# pcb.net
KiCad netlist of a schematic drawn in EAGLE
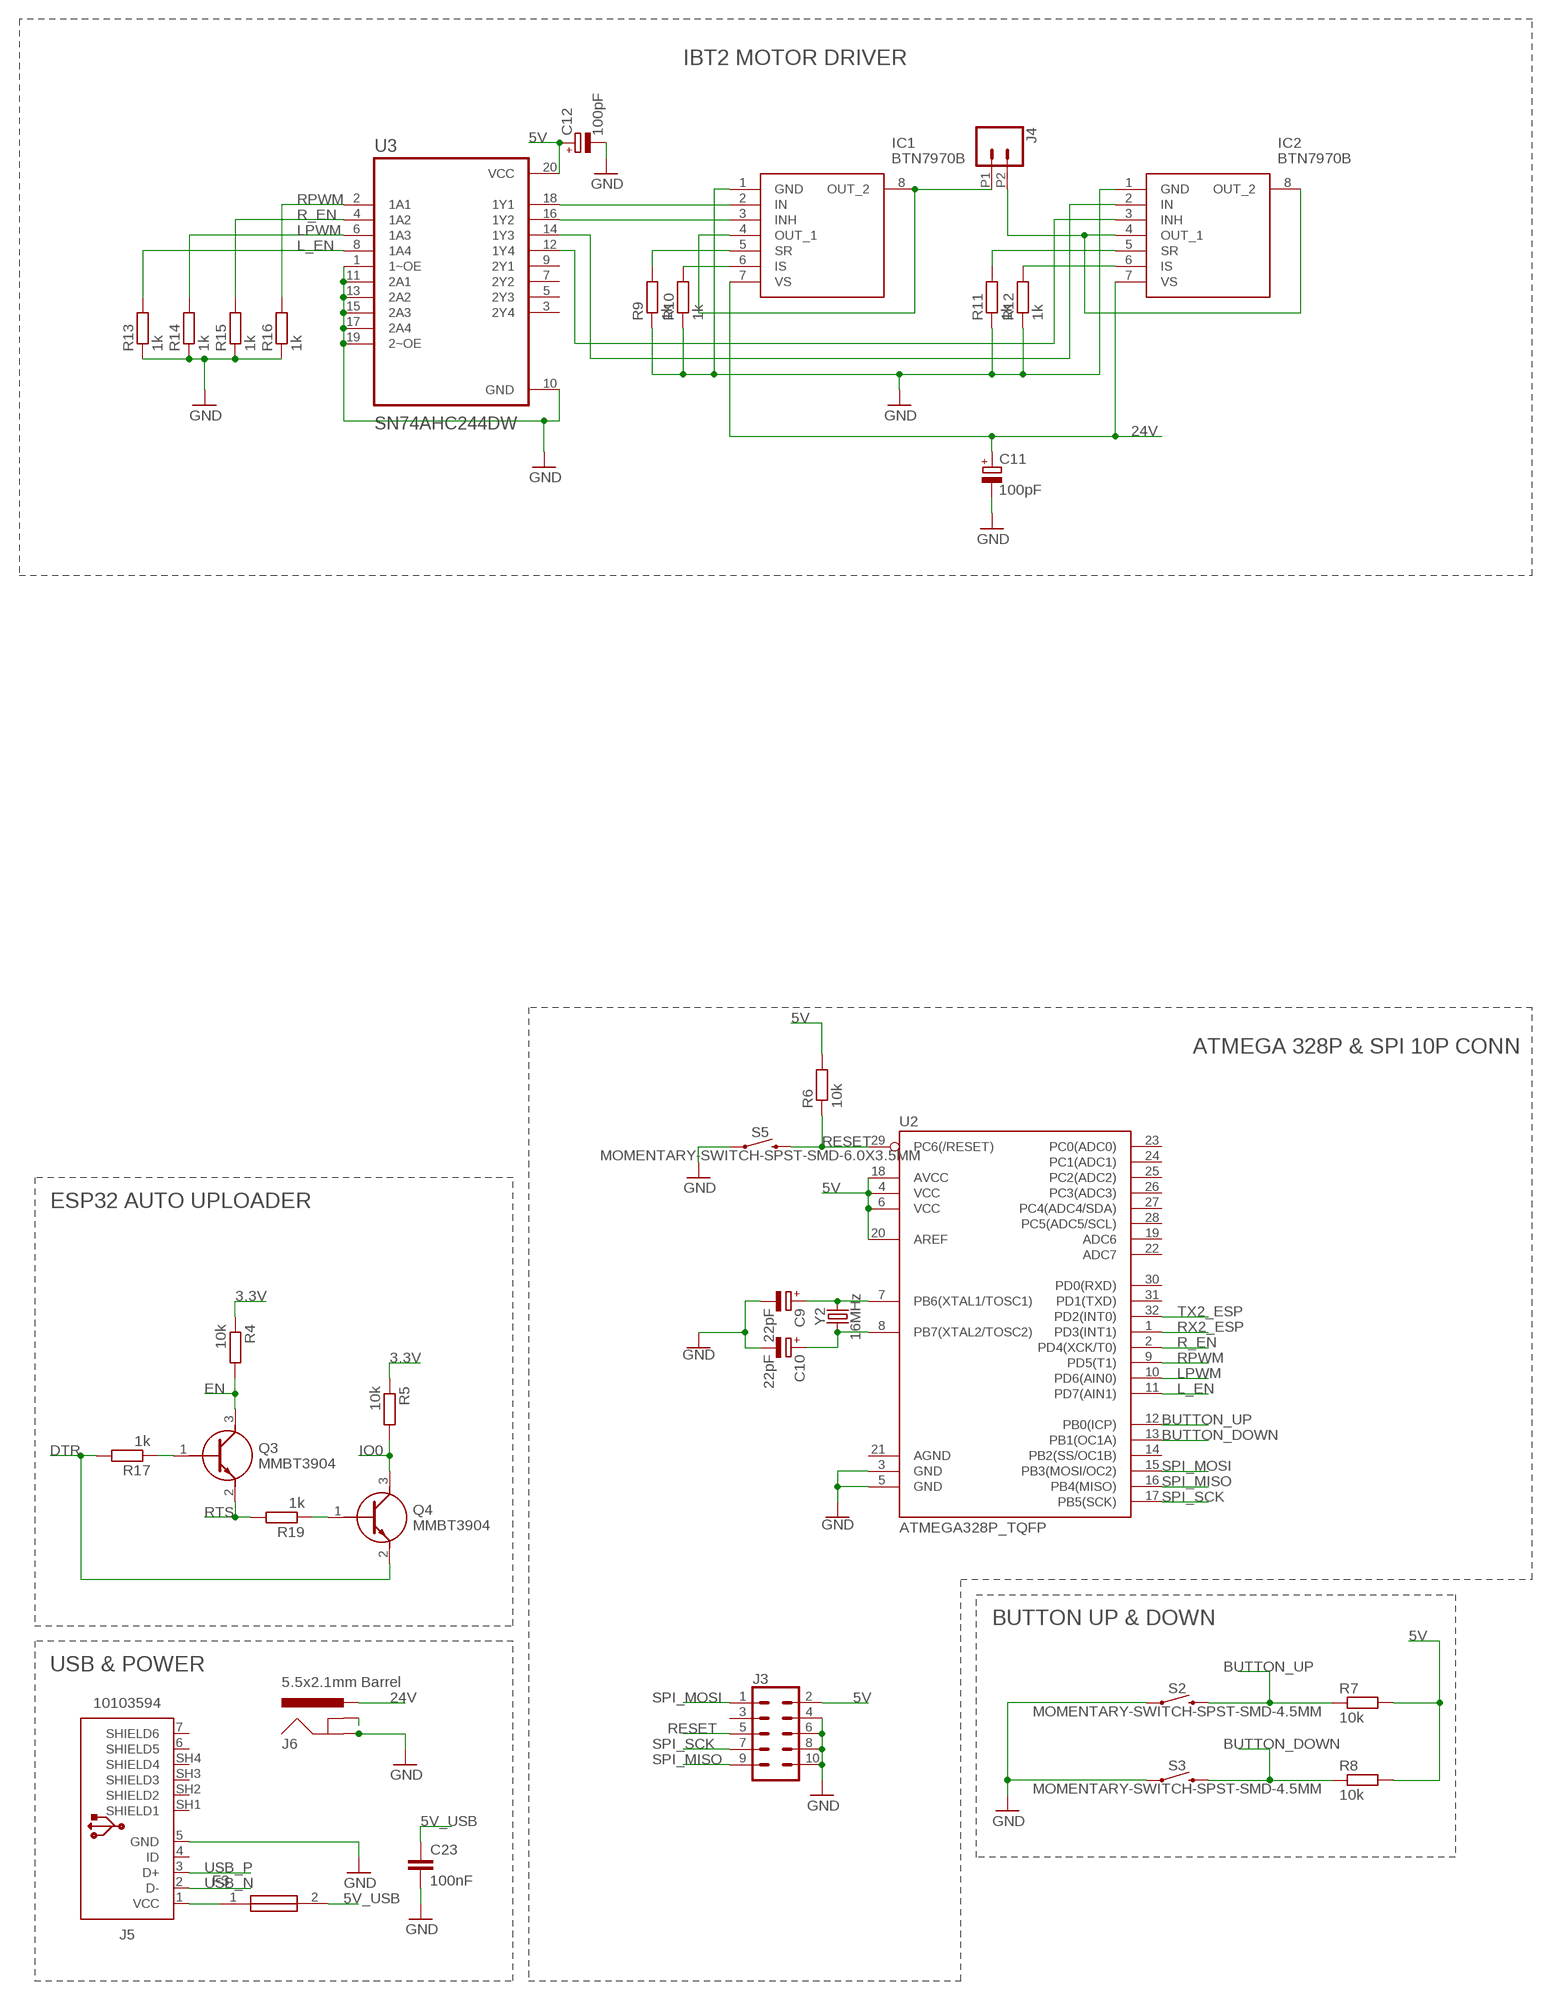
[diagram p0: schematic, sheet 1, part 1 of 2]
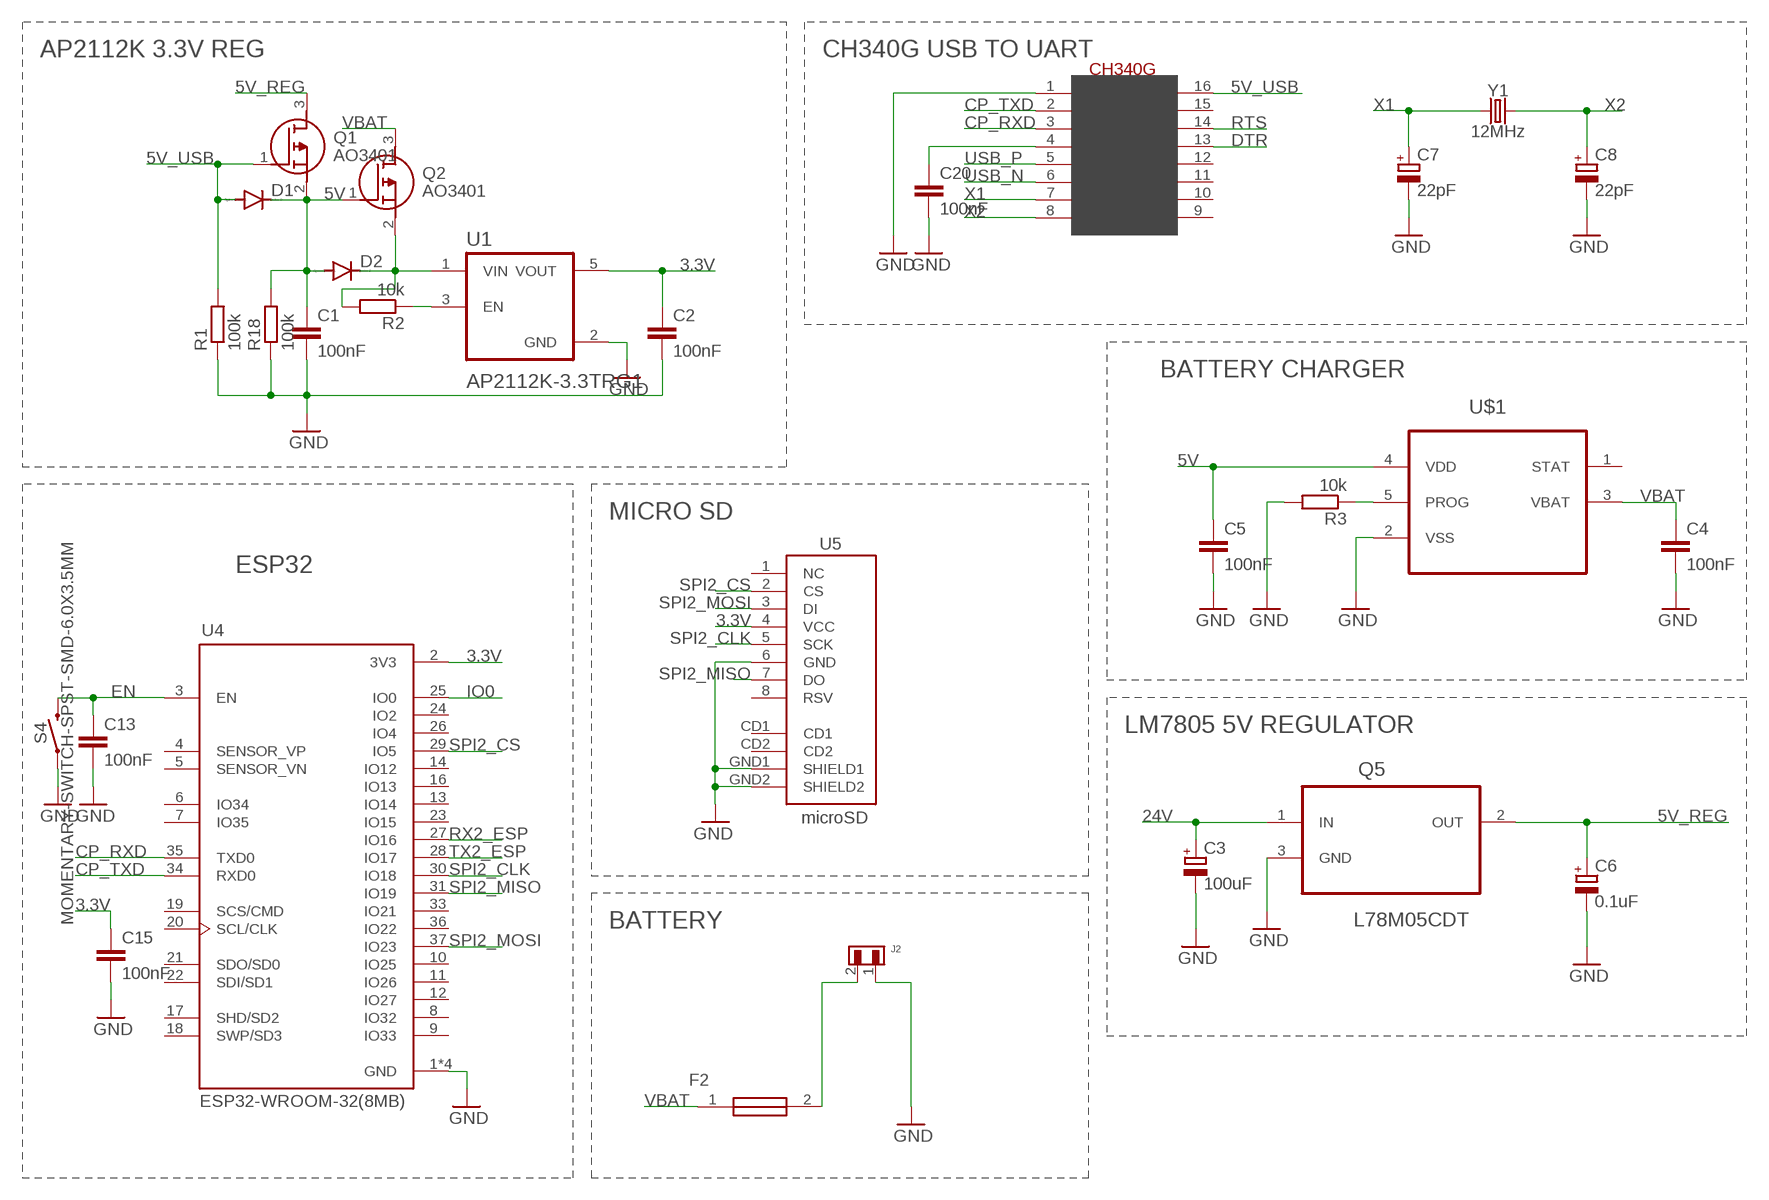
[diagram p1: schematic, sheet 1, part 2 of 2]

(export (version "E")
  (design (tool "Eeschema 10.0.6"))
  (components
    (comp (ref "C1")
      (value "100nF")
      (footprint "eagle-import:C0603")
      (libsource (lib "eagle-import") (part "C-EUC0603"))
    )
    (comp (ref "C2")
      (value "100nF")
      (footprint "eagle-import:C0603")
      (libsource (lib "eagle-import") (part "C-EUC0603"))
    )
    (comp (ref "C3")
      (value "100uF")
      (footprint "eagle-import:SMC_C")
      (libsource (lib "eagle-import") (part "CPOL-EUSMCC"))
    )
    (comp (ref "C4")
      (value "100nF")
      (footprint "eagle-import:C0603")
      (libsource (lib "eagle-import") (part "C-EUC0603"))
    )
    (comp (ref "C5")
      (value "100nF")
      (footprint "eagle-import:C0603")
      (libsource (lib "eagle-import") (part "C-EUC0603"))
    )
    (comp (ref "C6")
      (value "0.1uF")
      (footprint "eagle-import:SMC_C")
      (libsource (lib "eagle-import") (part "CPOL-EUSMCC"))
    )
    (comp (ref "C7")
      (value "22pF")
      (footprint "eagle-import:SMC_C")
      (libsource (lib "eagle-import") (part "CPOL-EUSMCC"))
    )
    (comp (ref "C8")
      (value "22pF")
      (footprint "eagle-import:SMC_C")
      (libsource (lib "eagle-import") (part "CPOL-EUSMCC"))
    )
    (comp (ref "C9")
      (value "22pF")
      (footprint "eagle-import:SMC_C")
      (libsource (lib "eagle-import") (part "CPOL-EUSMCC"))
    )
    (comp (ref "C10")
      (value "22pF")
      (footprint "eagle-import:SMC_C")
      (libsource (lib "eagle-import") (part "CPOL-EUSMCC"))
    )
    (comp (ref "C11")
      (value "100pF")
      (footprint "eagle-import:SMC_C")
      (libsource (lib "eagle-import") (part "CPOL-EUSMCC"))
    )
    (comp (ref "C12")
      (value "100pF")
      (footprint "eagle-import:SMC_C")
      (libsource (lib "eagle-import") (part "CPOL-EUSMCC"))
    )
    (comp (ref "C13")
      (value "100nF")
      (footprint "eagle-import:C0603")
      (libsource (lib "eagle-import") (part "C-EUC0603"))
    )
    (comp (ref "C15")
      (value "100nF")
      (footprint "eagle-import:C0603")
      (libsource (lib "eagle-import") (part "C-EUC0603"))
    )
    (comp (ref "C20")
      (value "100nF")
      (footprint "eagle-import:C0603")
      (libsource (lib "eagle-import") (part "C-EUC0603"))
    )
    (comp (ref "C23")
      (value "100nF")
      (footprint "eagle-import:C0603")
      (libsource (lib "eagle-import") (part "C-EUC0603"))
    )
    (comp (ref "D1")
      (value "DIODE-DO214AC")
      (footprint "eagle-import:DO214AC")
      (libsource (lib "eagle-import") (part "DIODE-DO214AC"))
    )
    (comp (ref "D2")
      (value "DIODE-DO214AC")
      (footprint "eagle-import:DO214AC")
      (libsource (lib "eagle-import") (part "DIODE-DO214AC"))
    )
    (comp (ref "F2")
      (value "MF-NSML260_12-2")
      (footprint "eagle-import:FUSC3216X100N")
      (fields
        (field (name "ARROW_PART_NUMBER") "MF-NSML260/12-2")
        (field (name "MOUSER_PART_NUMBER") "652-MF-NSML260/12-2")
      )
      (libsource (lib "eagle-import") (part "MF-NSML260_12-2"))
    )
    (comp (ref "F3")
      (value "MF-NSML260_12-2")
      (footprint "eagle-import:FUSC3216X100N")
      (fields
        (field (name "ARROW_PART_NUMBER") "MF-NSML260/12-2")
        (field (name "MOUSER_PART_NUMBER") "652-MF-NSML260/12-2")
      )
      (libsource (lib "eagle-import") (part "MF-NSML260_12-2"))
    )
    (comp (ref "IC1")
      (value "BTN7970B")
      (footprint "eagle-import:PG-TO263-7-1")
      (fields (field (name "MOUSER_PART_NUMBER") "726-BTN7970B"))
      (libsource (lib "eagle-import") (part "BTN7970B"))
    )
    (comp (ref "IC2")
      (value "BTN7970B")
      (footprint "eagle-import:PG-TO263-7-1")
      (fields (field (name "MOUSER_PART_NUMBER") "726-BTN7970B"))
      (libsource (lib "eagle-import") (part "BTN7970B"))
    )
    (comp (ref "J2")
      (value "620102131822")
      (footprint "eagle-import:620102131822")
      (libsource (lib "eagle-import") (part "620102131822"))
    )
    (comp (ref "J3")
      (value "CONN_05X2SHD-NS")
      (footprint "eagle-import:2X5-SHROUDED-NS")
      (libsource (lib "eagle-import") (part "CONN_05X2SHD-NS"))
    )
    (comp (ref "J4")
      (value "CONN_022.54MM_SCREWTERM")
      (footprint "eagle-import:1X02_2.54_SCREWTERM")
      (libsource (lib "eagle-import") (part "CONN_022.54MM_SCREWTERM"))
    )
    (comp (ref "J5")
      (value "10103594")
      (footprint "eagle-import:10103594")
      (fields (field (name "MANUFACTURER") "Amphenol ICC (FCI)") (field (name "MPN") "10103594-0001LF"))
      (libsource (lib "eagle-import") (part "10103594"))
    )
    (comp (ref "J6")
      (value "5.5x2.1mm Barrel")
      (footprint "eagle-import:POWER_JACK_SMD")
      (libsource (lib "eagle-import") (part "POWER_JACKSMD"))
    )
    (comp (ref "Q1")
      (value "AO3401")
      (footprint "eagle-import:SOT95P280X125-3N")
      (fields (field (name "ARROW_PART_NUMBER") "AO3401A"))
      (libsource (lib "eagle-import") (part "AO3401A"))
    )
    (comp (ref "Q2")
      (value "AO3401")
      (footprint "eagle-import:SOT95P280X125-3N")
      (fields (field (name "ARROW_PART_NUMBER") "AO3401A"))
      (libsource (lib "eagle-import") (part "AO3401A"))
    )
    (comp (ref "Q3")
      (value "MMBT3904")
      (footprint "eagle-import:SOT95P240X120-3N")
      (fields (field (name "MOUSER_PART_NUMBER") "512-MMBT3904"))
      (libsource (lib "eagle-import") (part "MMBT3904"))
    )
    (comp (ref "Q4")
      (value "MMBT3904")
      (footprint "eagle-import:SOT95P240X120-3N")
      (fields (field (name "MOUSER_PART_NUMBER") "512-MMBT3904"))
      (libsource (lib "eagle-import") (part "MMBT3904"))
    )
    (comp (ref "Q5")
      (value "L78M05CDT")
      (footprint "eagle-import:TO225P972X240-3N")
      (fields (field (name "MF") "STMicroelectronics"))
      (libsource (lib "eagle-import") (part "L78M05CDT"))
    )
    (comp (ref "R1")
      (value "100k")
      (footprint "eagle-import:R0603")
      (libsource (lib "eagle-import") (part "R-EU_R0603"))
    )
    (comp (ref "R2")
      (value "10k")
      (footprint "eagle-import:R0603")
      (libsource (lib "eagle-import") (part "R-EU_R0603"))
    )
    (comp (ref "R3")
      (value "10k")
      (footprint "eagle-import:R0603")
      (libsource (lib "eagle-import") (part "R-EU_R0603"))
    )
    (comp (ref "R4")
      (value "10k")
      (footprint "eagle-import:R0603")
      (libsource (lib "eagle-import") (part "R-EU_R0603"))
    )
    (comp (ref "R5")
      (value "10k")
      (footprint "eagle-import:R0603")
      (libsource (lib "eagle-import") (part "R-EU_R0603"))
    )
    (comp (ref "R6")
      (value "10k")
      (footprint "eagle-import:R0603")
      (libsource (lib "eagle-import") (part "R-EU_R0603"))
    )
    (comp (ref "R7")
      (value "10k")
      (footprint "eagle-import:R0603")
      (libsource (lib "eagle-import") (part "R-EU_R0603"))
    )
    (comp (ref "R8")
      (value "10k")
      (footprint "eagle-import:R0603")
      (libsource (lib "eagle-import") (part "R-EU_R0603"))
    )
    (comp (ref "R9")
      (value "1k")
      (footprint "eagle-import:R0603")
      (libsource (lib "eagle-import") (part "R-EU_R0603"))
    )
    (comp (ref "R10")
      (value "1k")
      (footprint "eagle-import:R0603")
      (libsource (lib "eagle-import") (part "R-EU_R0603"))
    )
    (comp (ref "R11")
      (value "1k")
      (footprint "eagle-import:R0603")
      (libsource (lib "eagle-import") (part "R-EU_R0603"))
    )
    (comp (ref "R12")
      (value "1k")
      (footprint "eagle-import:R0603")
      (libsource (lib "eagle-import") (part "R-EU_R0603"))
    )
    (comp (ref "R13")
      (value "1k")
      (footprint "eagle-import:R0603")
      (libsource (lib "eagle-import") (part "R-EU_R0603"))
    )
    (comp (ref "R14")
      (value "1k")
      (footprint "eagle-import:R0603")
      (libsource (lib "eagle-import") (part "R-EU_R0603"))
    )
    (comp (ref "R15")
      (value "1k")
      (footprint "eagle-import:R0603")
      (libsource (lib "eagle-import") (part "R-EU_R0603"))
    )
    (comp (ref "R16")
      (value "1k")
      (footprint "eagle-import:R0603")
      (libsource (lib "eagle-import") (part "R-EU_R0603"))
    )
    (comp (ref "R17")
      (value "1k")
      (footprint "eagle-import:R0603")
      (libsource (lib "eagle-import") (part "R-EU_R0603"))
    )
    (comp (ref "R18")
      (value "100k")
      (footprint "eagle-import:R0603")
      (libsource (lib "eagle-import") (part "R-EU_R0603"))
    )
    (comp (ref "R19")
      (value "1k")
      (footprint "eagle-import:R0603")
      (libsource (lib "eagle-import") (part "R-EU_R0603"))
    )
    (comp (ref "S2")
      (value "MOMENTARY-SWITCH-SPST-SMD-4.5MM")
      (footprint "eagle-import:TACTILE_SWITCH_SMD_4.5MM")
      (libsource (lib "eagle-import") (part "MOMENTARY-SWITCH-SPST-SMD-4.5MM"))
    )
    (comp (ref "S3")
      (value "MOMENTARY-SWITCH-SPST-SMD-4.5MM")
      (footprint "eagle-import:TACTILE_SWITCH_SMD_4.5MM")
      (libsource (lib "eagle-import") (part "MOMENTARY-SWITCH-SPST-SMD-4.5MM"))
    )
    (comp (ref "S4")
      (value "MOMENTARY-SWITCH-SPST-SMD-6.0X3.5MM")
      (footprint "eagle-import:TACTILE_SWITCH_SMD_6.0X3.5MM")
      (libsource (lib "eagle-import") (part "MOMENTARY-SWITCH-SPST-SMD-6.0X3.5MM"))
    )
    (comp (ref "S5")
      (value "MOMENTARY-SWITCH-SPST-SMD-6.0X3.5MM")
      (footprint "eagle-import:TACTILE_SWITCH_SMD_6.0X3.5MM")
      (libsource (lib "eagle-import") (part "MOMENTARY-SWITCH-SPST-SMD-6.0X3.5MM"))
    )
    (comp (ref "U$1")
      (value "MCP73831T-5ACI/OT")
      (footprint "eagle-import:SOT95P280X145-5N")
      (fields (field (name "MF") "Microchip"))
      (libsource (lib "eagle-import") (part "MCP73831T-5ACI/OT"))
    )
    (comp (ref "U$2")
      (value "CH340G")
      (footprint "eagle-import:SOIC16")
      (libsource (lib "eagle-import") (part "CH340G"))
    )
    (comp (ref "U1")
      (value "AP2112K-3.3TRG1")
      (footprint "eagle-import:SOT95P285X140-5N")
      (fields (field (name "MF") "Diodes Inc."))
      (libsource (lib "eagle-import") (part "AP2112K-3.3TRG1"))
    )
    (comp (ref "U2")
      (value "ATMEGA328P_TQFP")
      (footprint "eagle-import:TQFP32-08")
      (libsource (lib "eagle-import") (part "ATMEGA328P_TQFP"))
    )
    (comp (ref "U3")
      (value "SN74AHC244DW")
      (footprint "eagle-import:SOIC127P1030X265-20N")
      (fields (field (name "MF") "Texas Instruments"))
      (libsource (lib "eagle-import") (part "SN74AHC244DW"))
    )
    (comp (ref "U4")
      (value "ESP32-WROOM-32(8MB)")
      (footprint "eagle-import:MODULE_ESP32-WROOM-32(8MB)")
      (fields (field (name "MF") "Espressif Systems") (field (name "MP") "ESP32-WROOM-32 (8MB)"))
      (libsource (lib "eagle-import") (part "ESP32-WROOM-32(8MB)"))
    )
    (comp (ref "U5")
      (value "microSD")
      (footprint "eagle-import:MICRO-SD-SOCKET-PP")
      (libsource (lib "eagle-import") (part "USD-SOCKETSMD"))
    )
    (comp (ref "Y1")
      (value "12MHz")
      (footprint "eagle-import:CRYSTAL-SMD-5X3.2-4PAD")
      (libsource (lib "eagle-import") (part "CRYSTAL-12MHZ{dblquote}"))
    )
    (comp (ref "Y2")
      (value "16MHz")
      (footprint "eagle-import:CRYSTAL-SMD-5X3.2-4PAD")
      (libsource (lib "eagle-import") (part "CRYSTAL-16MHZSMD-5X3.2"))
    )
  )
  (nets
    (net (code "1") (name "/3.3V") (class "Default")
      (node (ref "C15") (pin "1") (pinfunction "1_1") (pintype "passive"))
      (node (ref "C2") (pin "1") (pinfunction "1_1") (pintype "passive"))
      (node (ref "R4") (pin "1") (pinfunction "1_1") (pintype "passive"))
      (node (ref "R5") (pin "1") (pinfunction "1_1") (pintype "passive"))
      (node (ref "U1") (pin "5") (pinfunction "VOUT_5") (pintype "power_in"))
      (node (ref "U4") (pin "2") (pinfunction "3V3_2") (pintype "power_in"))
      (node (ref "U5") (pin "4") (pinfunction "VCC_4") (pintype "bidirectional"))
    )
    (net (code "2") (name "/5V") (class "Default")
      (node (ref "C1") (pin "1") (pinfunction "1_1") (pintype "passive"))
      (node (ref "C12") (pin "+") (pinfunction "+_+") (pintype "passive"))
      (node (ref "C5") (pin "1") (pinfunction "1_1") (pintype "passive"))
      (node (ref "D1") (pin "C") (pinfunction "C_C") (pintype "passive"))
      (node (ref "D2") (pin "A") (pinfunction "A_A") (pintype "passive"))
      (node (ref "J3") (pin "2") (pinfunction "2_2") (pintype "passive"))
      (node (ref "Q1") (pin "2") (pinfunction "S_2") (pintype "bidirectional"))
      (node (ref "Q2") (pin "1") (pinfunction "G_1") (pintype "bidirectional"))
      (node (ref "R18") (pin "2") (pinfunction "2_2") (pintype "passive"))
      (node (ref "R6") (pin "2") (pinfunction "2_2") (pintype "passive"))
      (node (ref "R7") (pin "2") (pinfunction "2_2") (pintype "passive"))
      (node (ref "R8") (pin "2") (pinfunction "2_2") (pintype "passive"))
      (node (ref "U$1") (pin "4") (pinfunction "VDD_4") (pintype "power_in"))
      (node (ref "U2") (pin "18") (pinfunction "AVCC_18") (pintype "bidirectional"))
      (node (ref "U2") (pin "20") (pinfunction "AREF_20") (pintype "bidirectional"))
      (node (ref "U2") (pin "4") (pinfunction "VCC_4") (pintype "bidirectional"))
      (node (ref "U2") (pin "6") (pinfunction "VCC_6") (pintype "bidirectional"))
      (node (ref "U3") (pin "20") (pinfunction "VCC_20") (pintype "power_in"))
    )
    (net (code "3") (name "/5V_REG") (class "Default")
      (node (ref "C6") (pin "+") (pinfunction "+_+") (pintype "passive"))
      (node (ref "Q1") (pin "3") (pinfunction "D_3") (pintype "bidirectional"))
      (node (ref "Q5") (pin "2") (pinfunction "OUT_2") (pintype "output"))
    )
    (net (code "4") (name "/5V_USB") (class "Default")
      (node (ref "C23") (pin "1") (pinfunction "1_1") (pintype "passive"))
      (node (ref "D1") (pin "A") (pinfunction "A_A") (pintype "passive"))
      (node (ref "F3") (pin "2") (pinfunction "2_2") (pintype "bidirectional"))
      (node (ref "Q1") (pin "1") (pinfunction "G_1") (pintype "bidirectional"))
      (node (ref "R1") (pin "2") (pinfunction "2_2") (pintype "passive"))
      (node (ref "U$2") (pin "16") (pinfunction "VCC_16") (pintype "bidirectional"))
    )
    (net (code "5") (name "/24V") (class "Default")
      (node (ref "C11") (pin "+") (pinfunction "+_+") (pintype "passive"))
      (node (ref "C3") (pin "+") (pinfunction "+_+") (pintype "passive"))
      (node (ref "IC1") (pin "7") (pinfunction "VS_7") (pintype "bidirectional"))
      (node (ref "IC2") (pin "7") (pinfunction "VS_7") (pintype "bidirectional"))
      (node (ref "J6") (pin "VIN0") (pinfunction "PWR_VIN0") (pintype "bidirectional"))
      (node (ref "Q5") (pin "1") (pinfunction "IN_1") (pintype "input"))
    )
    (net (code "6") (name "/BUTTON_DOWN") (class "Default")
      (node (ref "R8") (pin "1") (pinfunction "1_1") (pintype "passive"))
      (node (ref "S3") (pin "1") (pinfunction "2_1") (pintype "passive"))
      (node (ref "S3") (pin "4") (pinfunction "2_4") (pintype "passive"))
      (node (ref "U2") (pin "13") (pinfunction "PB1(OC1A)_13") (pintype "bidirectional"))
    )
    (net (code "7") (name "/BUTTON_UP") (class "Default")
      (node (ref "R7") (pin "1") (pinfunction "1_1") (pintype "passive"))
      (node (ref "S2") (pin "1") (pinfunction "2_1") (pintype "passive"))
      (node (ref "S2") (pin "4") (pinfunction "2_4") (pintype "passive"))
      (node (ref "U2") (pin "12") (pinfunction "PB0(ICP)_12") (pintype "bidirectional"))
    )
    (net (code "8") (name "/CP_RXD") (class "Default")
      (node (ref "U$2") (pin "3") (pinfunction "RX_3") (pintype "bidirectional"))
      (node (ref "U4") (pin "35") (pinfunction "TXD0_35") (pintype "bidirectional"))
    )
    (net (code "9") (name "/CP_TXD") (class "Default")
      (node (ref "U$2") (pin "2") (pinfunction "TX_2") (pintype "bidirectional"))
      (node (ref "U4") (pin "34") (pinfunction "RXD0_34") (pintype "bidirectional"))
    )
    (net (code "10") (name "/DTR") (class "Default")
      (node (ref "Q4") (pin "2") (pinfunction "E_2") (pintype "bidirectional"))
      (node (ref "R17") (pin "2") (pinfunction "2_2") (pintype "passive"))
      (node (ref "U$2") (pin "13") (pinfunction "DTR_13") (pintype "bidirectional"))
    )
    (net (code "11") (name "/EN") (class "Default")
      (node (ref "C13") (pin "1") (pinfunction "1_1") (pintype "passive"))
      (node (ref "Q3") (pin "3") (pinfunction "C_3") (pintype "bidirectional"))
      (node (ref "R4") (pin "2") (pinfunction "2_2") (pintype "passive"))
      (node (ref "S4") (pin "2") (pinfunction "2_2") (pintype "passive"))
      (node (ref "U4") (pin "3") (pinfunction "EN_3") (pintype "input"))
    )
    (net (code "12") (name "/IO0") (class "Default")
      (node (ref "Q4") (pin "3") (pinfunction "C_3") (pintype "bidirectional"))
      (node (ref "R5") (pin "2") (pinfunction "2_2") (pintype "passive"))
      (node (ref "U4") (pin "25") (pinfunction "IO0_25") (pintype "bidirectional"))
    )
    (net (code "13") (name "/LPWM") (class "Default")
      (node (ref "R14") (pin "2") (pinfunction "2_2") (pintype "passive"))
      (node (ref "U2") (pin "10") (pinfunction "PD6(AIN0)_10") (pintype "bidirectional"))
      (node (ref "U3") (pin "6") (pinfunction "1A3_6") (pintype "input"))
    )
    (net (code "14") (name "/L_EN") (class "Default")
      (node (ref "R13") (pin "2") (pinfunction "2_2") (pintype "passive"))
      (node (ref "U2") (pin "11") (pinfunction "PD7(AIN1)_11") (pintype "bidirectional"))
      (node (ref "U3") (pin "8") (pinfunction "1A4_8") (pintype "input"))
    )
    (net (code "15") (name "/RESET") (class "Default")
      (node (ref "J3") (pin "5") (pinfunction "5_5") (pintype "passive"))
      (node (ref "R6") (pin "1") (pinfunction "1_1") (pintype "passive"))
      (node (ref "S5") (pin "2") (pinfunction "2_2") (pintype "passive"))
      (node (ref "U2") (pin "29") (pinfunction "PC6(/RESET)_29") (pintype "bidirectional"))
    )
    (net (code "16") (name "/RPWM") (class "Default")
      (node (ref "R16") (pin "2") (pinfunction "2_2") (pintype "passive"))
      (node (ref "U2") (pin "9") (pinfunction "PD5(T1)_9") (pintype "bidirectional"))
      (node (ref "U3") (pin "2") (pinfunction "1A1_2") (pintype "input"))
    )
    (net (code "17") (name "/RTS") (class "Default")
      (node (ref "Q3") (pin "2") (pinfunction "E_2") (pintype "bidirectional"))
      (node (ref "R19") (pin "2") (pinfunction "2_2") (pintype "passive"))
      (node (ref "U$2") (pin "14") (pinfunction "RTS_14") (pintype "bidirectional"))
    )
    (net (code "18") (name "/RX2_ESP") (class "Default")
      (node (ref "U2") (pin "1") (pinfunction "PD3(INT1)_1") (pintype "bidirectional"))
      (node (ref "U4") (pin "27") (pinfunction "IO16_27") (pintype "bidirectional"))
    )
    (net (code "19") (name "/R_EN") (class "Default")
      (node (ref "R15") (pin "2") (pinfunction "2_2") (pintype "passive"))
      (node (ref "U2") (pin "2") (pinfunction "PD4(XCK/T0)_2") (pintype "bidirectional"))
      (node (ref "U3") (pin "4") (pinfunction "1A2_4") (pintype "input"))
    )
    (net (code "20") (name "/SHIELD1") (class "Default")
      (node (ref "J5") (pin "SH1") (pinfunction "SHIELD1_SH1") (pintype "power_in"))
    )
    (net (code "21") (name "/SHIELD2") (class "Default")
      (node (ref "J5") (pin "SH2") (pinfunction "SHIELD2_SH2") (pintype "power_in"))
    )
    (net (code "22") (name "/SHIELD3") (class "Default")
      (node (ref "J5") (pin "SH3") (pinfunction "SHIELD3_SH3") (pintype "power_in"))
    )
    (net (code "23") (name "/SHIELD4") (class "Default")
      (node (ref "J5") (pin "SH4") (pinfunction "SHIELD4_SH4") (pintype "power_in"))
    )
    (net (code "24") (name "/SHIELD5") (class "Default")
      (node (ref "J5") (pin "6") (pinfunction "SHIELD5_6") (pintype "power_in"))
    )
    (net (code "25") (name "/SHIELD6") (class "Default")
      (node (ref "J5") (pin "7") (pinfunction "SHIELD6_7") (pintype "power_in"))
    )
    (net (code "26") (name "/SPI2_CLK") (class "Default")
      (node (ref "U4") (pin "30") (pinfunction "IO18_30") (pintype "bidirectional"))
      (node (ref "U5") (pin "5") (pinfunction "SCK_5") (pintype "bidirectional"))
    )
    (net (code "27") (name "/SPI2_CS") (class "Default")
      (node (ref "U4") (pin "29") (pinfunction "IO5_29") (pintype "bidirectional"))
      (node (ref "U5") (pin "2") (pinfunction "CS_2") (pintype "bidirectional"))
    )
    (net (code "28") (name "/SPI2_MISO") (class "Default")
      (node (ref "U4") (pin "31") (pinfunction "IO19_31") (pintype "bidirectional"))
      (node (ref "U5") (pin "7") (pinfunction "DO_7") (pintype "bidirectional"))
    )
    (net (code "29") (name "/SPI2_MOSI") (class "Default")
      (node (ref "U4") (pin "37") (pinfunction "IO23_37") (pintype "bidirectional"))
      (node (ref "U5") (pin "3") (pinfunction "DI_3") (pintype "bidirectional"))
    )
    (net (code "30") (name "/SPI_MISO") (class "Default")
      (node (ref "J3") (pin "9") (pinfunction "9_9") (pintype "passive"))
      (node (ref "U2") (pin "16") (pinfunction "PB4(MISO)_16") (pintype "bidirectional"))
    )
    (net (code "31") (name "/SPI_MOSI") (class "Default")
      (node (ref "J3") (pin "1") (pinfunction "1_1") (pintype "passive"))
      (node (ref "U2") (pin "15") (pinfunction "PB3(MOSI/OC2)_15") (pintype "bidirectional"))
    )
    (net (code "32") (name "/SPI_SCK") (class "Default")
      (node (ref "J3") (pin "7") (pinfunction "7_7") (pintype "passive"))
      (node (ref "U2") (pin "17") (pinfunction "PB5(SCK)_17") (pintype "bidirectional"))
    )
    (net (code "33") (name "/TX2_ESP") (class "Default")
      (node (ref "U2") (pin "32") (pinfunction "PD2(INT0)_32") (pintype "bidirectional"))
      (node (ref "U4") (pin "28") (pinfunction "IO17_28") (pintype "bidirectional"))
    )
    (net (code "34") (name "/USB_N") (class "Default")
      (node (ref "J5") (pin "2") (pinfunction "D-_2") (pintype "bidirectional"))
      (node (ref "U$2") (pin "6") (pinfunction "D-_6") (pintype "bidirectional"))
    )
    (net (code "35") (name "/USB_P") (class "Default")
      (node (ref "J5") (pin "3") (pinfunction "D+_3") (pintype "bidirectional"))
      (node (ref "U$2") (pin "5") (pinfunction "D+_5") (pintype "bidirectional"))
    )
    (net (code "36") (name "/VBAT") (class "Default")
      (node (ref "C4") (pin "1") (pinfunction "1_1") (pintype "passive"))
      (node (ref "F2") (pin "1") (pinfunction "1_1") (pintype "bidirectional"))
      (node (ref "Q2") (pin "3") (pinfunction "D_3") (pintype "bidirectional"))
      (node (ref "U$1") (pin "3") (pinfunction "VBAT_3") (pintype "output"))
    )
    (net (code "37") (name "/X1") (class "Default")
      (node (ref "C7") (pin "+") (pinfunction "+_+") (pintype "passive"))
      (node (ref "U$2") (pin "7") (pinfunction "XI_7") (pintype "bidirectional"))
      (node (ref "Y1") (pin "1") (pinfunction "1_1") (pintype "passive"))
    )
    (net (code "38") (name "/X2") (class "Default")
      (node (ref "C8") (pin "+") (pinfunction "+_+") (pintype "passive"))
      (node (ref "U$2") (pin "8") (pinfunction "XO_8") (pintype "bidirectional"))
      (node (ref "Y1") (pin "3") (pinfunction "2_3") (pintype "passive"))
    )
    (net (code "39") (name "GND") (class "Default")
      (node (ref "C1") (pin "2") (pinfunction "2_2") (pintype "passive"))
      (node (ref "C10") (pin "-") (pinfunction "-_-") (pintype "passive"))
      (node (ref "C11") (pin "-") (pinfunction "-_-") (pintype "passive"))
      (node (ref "C12") (pin "-") (pinfunction "-_-") (pintype "passive"))
      (node (ref "C13") (pin "2") (pinfunction "2_2") (pintype "passive"))
      (node (ref "C15") (pin "2") (pinfunction "2_2") (pintype "passive"))
      (node (ref "C2") (pin "2") (pinfunction "2_2") (pintype "passive"))
      (node (ref "C20") (pin "2") (pinfunction "2_2") (pintype "passive"))
      (node (ref "C23") (pin "2") (pinfunction "2_2") (pintype "passive"))
      (node (ref "C3") (pin "-") (pinfunction "-_-") (pintype "passive"))
      (node (ref "C4") (pin "2") (pinfunction "2_2") (pintype "passive"))
      (node (ref "C5") (pin "2") (pinfunction "2_2") (pintype "passive"))
      (node (ref "C6") (pin "-") (pinfunction "-_-") (pintype "passive"))
      (node (ref "C7") (pin "-") (pinfunction "-_-") (pintype "passive"))
      (node (ref "C8") (pin "-") (pinfunction "-_-") (pintype "passive"))
      (node (ref "C9") (pin "-") (pinfunction "-_-") (pintype "passive"))
      (node (ref "IC1") (pin "1") (pinfunction "GND_1") (pintype "bidirectional"))
      (node (ref "IC2") (pin "1") (pinfunction "GND_1") (pintype "bidirectional"))
      (node (ref "J2") (pin "1") (pinfunction "1_1") (pintype "passive"))
      (node (ref "J3") (pin "10") (pinfunction "10_10") (pintype "passive"))
      (node (ref "J3") (pin "4") (pinfunction "4_4") (pintype "passive"))
      (node (ref "J3") (pin "6") (pinfunction "6_6") (pintype "passive"))
      (node (ref "J3") (pin "8") (pinfunction "8_8") (pintype "passive"))
      (node (ref "J5") (pin "5") (pinfunction "GND_5") (pintype "power_in"))
      (node (ref "J6") (pin "P$4") (pinfunction "GND_P$4") (pintype "bidirectional"))
      (node (ref "Q5") (pin "3") (pinfunction "GND_3") (pintype "passive"))
      (node (ref "R1") (pin "1") (pinfunction "1_1") (pintype "passive"))
      (node (ref "R10") (pin "1") (pinfunction "1_1") (pintype "passive"))
      (node (ref "R11") (pin "1") (pinfunction "1_1") (pintype "passive"))
      (node (ref "R12") (pin "1") (pinfunction "1_1") (pintype "passive"))
      (node (ref "R13") (pin "1") (pinfunction "1_1") (pintype "passive"))
      (node (ref "R14") (pin "1") (pinfunction "1_1") (pintype "passive"))
      (node (ref "R15") (pin "1") (pinfunction "1_1") (pintype "passive"))
      (node (ref "R16") (pin "1") (pinfunction "1_1") (pintype "passive"))
      (node (ref "R18") (pin "1") (pinfunction "1_1") (pintype "passive"))
      (node (ref "R3") (pin "2") (pinfunction "2_2") (pintype "passive"))
      (node (ref "R9") (pin "1") (pinfunction "1_1") (pintype "passive"))
      (node (ref "S2") (pin "2") (pinfunction "1_2") (pintype "passive"))
      (node (ref "S2") (pin "3") (pinfunction "1_3") (pintype "passive"))
      (node (ref "S3") (pin "2") (pinfunction "1_2") (pintype "passive"))
      (node (ref "S3") (pin "3") (pinfunction "1_3") (pintype "passive"))
      (node (ref "S4") (pin "1") (pinfunction "1_1") (pintype "passive"))
      (node (ref "S5") (pin "1") (pinfunction "1_1") (pintype "passive"))
      (node (ref "U$1") (pin "2") (pinfunction "VSS_2") (pintype "power_in"))
      (node (ref "U$2") (pin "1") (pinfunction "GND_1") (pintype "bidirectional"))
      (node (ref "U1") (pin "2") (pinfunction "GND_2") (pintype "power_in"))
      (node (ref "U2") (pin "3") (pinfunction "GND_3") (pintype "bidirectional"))
      (node (ref "U2") (pin "5") (pinfunction "GND_5") (pintype "bidirectional"))
      (node (ref "U3") (pin "1") (pinfunction "1~{OE}_1") (pintype "input"))
      (node (ref "U3") (pin "10") (pinfunction "GND_10") (pintype "power_in"))
      (node (ref "U3") (pin "11") (pinfunction "2A1_11") (pintype "input"))
      (node (ref "U3") (pin "13") (pinfunction "2A2_13") (pintype "input"))
      (node (ref "U3") (pin "15") (pinfunction "2A3_15") (pintype "input"))
      (node (ref "U3") (pin "17") (pinfunction "2A4_17") (pintype "input"))
      (node (ref "U3") (pin "19") (pinfunction "2~{OE}_19") (pintype "input"))
      (node (ref "U4") (pin "1") (pinfunction "GND_1") (pintype "power_in"))
      (node (ref "U4") (pin "15") (pinfunction "GND_15") (pintype "power_in"))
      (node (ref "U4") (pin "38") (pinfunction "GND_38") (pintype "power_in"))
      (node (ref "U4") (pin "39") (pinfunction "GND_39") (pintype "power_in"))
      (node (ref "U5") (pin "6") (pinfunction "GND_6") (pintype "bidirectional"))
      (node (ref "U5") (pin "GND1") (pinfunction "SHIELD1_GND1") (pintype "bidirectional"))
      (node (ref "U5") (pin "GND2") (pinfunction "SHIELD2_GND2") (pintype "bidirectional"))
    )
    (net (code "40") (name "Net-(F2-Pad2)") (class "Default")
      (node (ref "F2") (pin "2") (pinfunction "2_2") (pintype "bidirectional"))
      (node (ref "J2") (pin "2") (pinfunction "2_2") (pintype "passive"))
    )
    (net (code "41") (name "Net-(IC1-IN)") (class "Default")
      (node (ref "IC1") (pin "2") (pinfunction "IN_2") (pintype "bidirectional"))
      (node (ref "U3") (pin "18") (pinfunction "1Y1_18") (pintype "output"))
    )
    (net (code "42") (name "Net-(IC1-INH)") (class "Default")
      (node (ref "IC1") (pin "3") (pinfunction "INH_3") (pintype "bidirectional"))
      (node (ref "U3") (pin "16") (pinfunction "1Y2_16") (pintype "output"))
    )
    (net (code "43") (name "Net-(IC1-IS)") (class "Default")
      (node (ref "IC1") (pin "6") (pinfunction "IS_6") (pintype "bidirectional"))
      (node (ref "R10") (pin "2") (pinfunction "2_2") (pintype "passive"))
    )
    (net (code "44") (name "Net-(IC1-OUT_1)") (class "Default")
      (node (ref "IC1") (pin "4") (pinfunction "OUT_1_4") (pintype "bidirectional"))
      (node (ref "IC1") (pin "8") (pinfunction "OUT_2_8") (pintype "bidirectional"))
      (node (ref "J4") (pin "P1") (pinfunction "1_P1") (pintype "passive"))
    )
    (net (code "45") (name "Net-(IC1-SR)") (class "Default")
      (node (ref "IC1") (pin "5") (pinfunction "SR_5") (pintype "bidirectional"))
      (node (ref "R9") (pin "2") (pinfunction "2_2") (pintype "passive"))
    )
    (net (code "46") (name "Net-(IC2-IN)") (class "Default")
      (node (ref "IC2") (pin "2") (pinfunction "IN_2") (pintype "bidirectional"))
      (node (ref "U3") (pin "14") (pinfunction "1Y3_14") (pintype "output"))
    )
    (net (code "47") (name "Net-(IC2-INH)") (class "Default")
      (node (ref "IC2") (pin "3") (pinfunction "INH_3") (pintype "bidirectional"))
      (node (ref "U3") (pin "12") (pinfunction "1Y4_12") (pintype "output"))
    )
    (net (code "48") (name "Net-(IC2-IS)") (class "Default")
      (node (ref "IC2") (pin "6") (pinfunction "IS_6") (pintype "bidirectional"))
      (node (ref "R12") (pin "2") (pinfunction "2_2") (pintype "passive"))
    )
    (net (code "49") (name "Net-(IC2-OUT_1)") (class "Default")
      (node (ref "IC2") (pin "4") (pinfunction "OUT_1_4") (pintype "bidirectional"))
      (node (ref "IC2") (pin "8") (pinfunction "OUT_2_8") (pintype "bidirectional"))
      (node (ref "J4") (pin "P2") (pinfunction "2_P2") (pintype "passive"))
    )
    (net (code "50") (name "Net-(IC2-SR)") (class "Default")
      (node (ref "IC2") (pin "5") (pinfunction "SR_5") (pintype "bidirectional"))
      (node (ref "R11") (pin "2") (pinfunction "2_2") (pintype "passive"))
    )
    (net (code "51") (name "Net-(J5-VCC)") (class "Default")
      (node (ref "F3") (pin "1") (pinfunction "1_1") (pintype "bidirectional"))
      (node (ref "J5") (pin "1") (pinfunction "VCC_1") (pintype "power_in"))
    )
    (net (code "52") (name "Net-(Q2-S)") (class "Default")
      (node (ref "D2") (pin "C") (pinfunction "C_C") (pintype "passive"))
      (node (ref "Q2") (pin "2") (pinfunction "S_2") (pintype "bidirectional"))
      (node (ref "R2") (pin "2") (pinfunction "2_2") (pintype "passive"))
      (node (ref "U1") (pin "1") (pinfunction "VIN_1") (pintype "power_in"))
    )
    (net (code "53") (name "Net-(Q3-B)") (class "Default")
      (node (ref "Q3") (pin "1") (pinfunction "B_1") (pintype "bidirectional"))
      (node (ref "R17") (pin "1") (pinfunction "1_1") (pintype "passive"))
    )
    (net (code "54") (name "Net-(Q4-B)") (class "Default")
      (node (ref "Q4") (pin "1") (pinfunction "B_1") (pintype "bidirectional"))
      (node (ref "R19") (pin "1") (pinfunction "1_1") (pintype "passive"))
    )
    (net (code "55") (name "Net-(U$1-PROG)") (class "Default")
      (node (ref "R3") (pin "1") (pinfunction "1_1") (pintype "passive"))
      (node (ref "U$1") (pin "5") (pinfunction "PROG_5") (pintype "input"))
    )
    (net (code "56") (name "Net-(U$2-V3)") (class "Default")
      (node (ref "C20") (pin "1") (pinfunction "1_1") (pintype "passive"))
      (node (ref "U$2") (pin "4") (pinfunction "V3_4") (pintype "bidirectional"))
    )
    (net (code "57") (name "Net-(U1-EN)") (class "Default")
      (node (ref "R2") (pin "1") (pinfunction "1_1") (pintype "passive"))
      (node (ref "U1") (pin "3") (pinfunction "EN_3") (pintype "input"))
    )
    (net (code "58") (name "Net-(U2-PB6(XTAL1{slash}TOSC1))") (class "Default")
      (node (ref "C9") (pin "+") (pinfunction "+_+") (pintype "passive"))
      (node (ref "U2") (pin "7") (pinfunction "PB6(XTAL1/TOSC1)_7") (pintype "bidirectional"))
      (node (ref "Y2") (pin "3") (pinfunction "2_3") (pintype "passive"))
    )
    (net (code "59") (name "Net-(U2-PB7(XTAL2{slash}TOSC2))") (class "Default")
      (node (ref "C10") (pin "+") (pinfunction "+_+") (pintype "passive"))
      (node (ref "U2") (pin "8") (pinfunction "PB7(XTAL2/TOSC2)_8") (pintype "bidirectional"))
      (node (ref "Y2") (pin "1") (pinfunction "1_1") (pintype "passive"))
    )
    (net (code "60") (name "unconnected-(J3-Pad3)") (class "Default")
      (node (ref "J3") (pin "3") (pinfunction "3_3") (pintype "passive"))
    )
    (net (code "61") (name "unconnected-(J5-ID-Pad4)") (class "Default")
      (node (ref "J5") (pin "4") (pinfunction "ID_4") (pintype "bidirectional"))
    )
    (net (code "62") (name "unconnected-(J6-GNDBREAK-PadGND)") (class "Default")
      (node (ref "J6") (pin "GND") (pinfunction "GNDBREAK_GND") (pintype "bidirectional"))
    )
    (net (code "63") (name "unconnected-(U$1-STAT-Pad1)") (class "Default")
      (node (ref "U$1") (pin "1") (pinfunction "STAT_1") (pintype "output"))
    )
    (net (code "64") (name "unconnected-(U$2-CTS-Pad9)") (class "Default")
      (node (ref "U$2") (pin "9") (pinfunction "CTS_9") (pintype "bidirectional"))
    )
    (net (code "65") (name "unconnected-(U$2-DCD-Pad12)") (class "Default")
      (node (ref "U$2") (pin "12") (pinfunction "DCD_12") (pintype "bidirectional"))
    )
    (net (code "66") (name "unconnected-(U$2-DSR-Pad10)") (class "Default")
      (node (ref "U$2") (pin "10") (pinfunction "DSR_10") (pintype "bidirectional"))
    )
    (net (code "67") (name "unconnected-(U$2-RI-Pad11)") (class "Default")
      (node (ref "U$2") (pin "11") (pinfunction "RI_11") (pintype "bidirectional"))
    )
    (net (code "68") (name "unconnected-(U$2-RS232-Pad15)") (class "Default")
      (node (ref "U$2") (pin "15") (pinfunction "RS232_15") (pintype "bidirectional"))
    )
    (net (code "69") (name "unconnected-(U2-ADC6-Pad19)") (class "Default")
      (node (ref "U2") (pin "19") (pinfunction "ADC6_19") (pintype "bidirectional"))
    )
    (net (code "70") (name "unconnected-(U2-ADC7-Pad22)") (class "Default")
      (node (ref "U2") (pin "22") (pinfunction "ADC7_22") (pintype "bidirectional"))
    )
    (net (code "71") (name "unconnected-(U2-AGND-Pad21)") (class "Default")
      (node (ref "U2") (pin "21") (pinfunction "AGND_21") (pintype "bidirectional"))
    )
    (net (code "72") (name "unconnected-(U2-PB2(SS{slash}OC1B)-Pad14)") (class "Default")
      (node (ref "U2") (pin "14") (pinfunction "PB2(SS/OC1B)_14") (pintype "bidirectional"))
    )
    (net (code "73") (name "unconnected-(U2-PC0(ADC0)-Pad23)") (class "Default")
      (node (ref "U2") (pin "23") (pinfunction "PC0(ADC0)_23") (pintype "bidirectional"))
    )
    (net (code "74") (name "unconnected-(U2-PC1(ADC1)-Pad24)") (class "Default")
      (node (ref "U2") (pin "24") (pinfunction "PC1(ADC1)_24") (pintype "bidirectional"))
    )
    (net (code "75") (name "unconnected-(U2-PC2(ADC2)-Pad25)") (class "Default")
      (node (ref "U2") (pin "25") (pinfunction "PC2(ADC2)_25") (pintype "bidirectional"))
    )
    (net (code "76") (name "unconnected-(U2-PC3(ADC3)-Pad26)") (class "Default")
      (node (ref "U2") (pin "26") (pinfunction "PC3(ADC3)_26") (pintype "bidirectional"))
    )
    (net (code "77") (name "unconnected-(U2-PC4(ADC4{slash}SDA)-Pad27)") (class "Default")
      (node (ref "U2") (pin "27") (pinfunction "PC4(ADC4/SDA)_27") (pintype "bidirectional"))
    )
    (net (code "78") (name "unconnected-(U2-PC5(ADC5{slash}SCL)-Pad28)") (class "Default")
      (node (ref "U2") (pin "28") (pinfunction "PC5(ADC5/SCL)_28") (pintype "bidirectional"))
    )
    (net (code "79") (name "unconnected-(U2-PD0(RXD)-Pad30)") (class "Default")
      (node (ref "U2") (pin "30") (pinfunction "PD0(RXD)_30") (pintype "bidirectional"))
    )
    (net (code "80") (name "unconnected-(U2-PD1(TXD)-Pad31)") (class "Default")
      (node (ref "U2") (pin "31") (pinfunction "PD1(TXD)_31") (pintype "bidirectional"))
    )
    (net (code "81") (name "unconnected-(U3-2Y1-Pad9)") (class "Default")
      (node (ref "U3") (pin "9") (pinfunction "2Y1_9") (pintype "output"))
    )
    (net (code "82") (name "unconnected-(U3-2Y2-Pad7)") (class "Default")
      (node (ref "U3") (pin "7") (pinfunction "2Y2_7") (pintype "output"))
    )
    (net (code "83") (name "unconnected-(U3-2Y3-Pad5)") (class "Default")
      (node (ref "U3") (pin "5") (pinfunction "2Y3_5") (pintype "output"))
    )
    (net (code "84") (name "unconnected-(U3-2Y4-Pad3)") (class "Default")
      (node (ref "U3") (pin "3") (pinfunction "2Y4_3") (pintype "output"))
    )
    (net (code "85") (name "unconnected-(U4-IO2-Pad24)") (class "Default")
      (node (ref "U4") (pin "24") (pinfunction "IO2_24") (pintype "bidirectional"))
    )
    (net (code "86") (name "unconnected-(U4-IO4-Pad26)") (class "Default")
      (node (ref "U4") (pin "26") (pinfunction "IO4_26") (pintype "bidirectional"))
    )
    (net (code "87") (name "unconnected-(U4-IO12-Pad14)") (class "Default")
      (node (ref "U4") (pin "14") (pinfunction "IO12_14") (pintype "bidirectional"))
    )
    (net (code "88") (name "unconnected-(U4-IO13-Pad16)") (class "Default")
      (node (ref "U4") (pin "16") (pinfunction "IO13_16") (pintype "bidirectional"))
    )
    (net (code "89") (name "unconnected-(U4-IO14-Pad13)") (class "Default")
      (node (ref "U4") (pin "13") (pinfunction "IO14_13") (pintype "bidirectional"))
    )
    (net (code "90") (name "unconnected-(U4-IO15-Pad23)") (class "Default")
      (node (ref "U4") (pin "23") (pinfunction "IO15_23") (pintype "bidirectional"))
    )
    (net (code "91") (name "unconnected-(U4-IO21-Pad33)") (class "Default")
      (node (ref "U4") (pin "33") (pinfunction "IO21_33") (pintype "bidirectional"))
    )
    (net (code "92") (name "unconnected-(U4-IO22-Pad36)") (class "Default")
      (node (ref "U4") (pin "36") (pinfunction "IO22_36") (pintype "bidirectional"))
    )
    (net (code "93") (name "unconnected-(U4-IO25-Pad10)") (class "Default")
      (node (ref "U4") (pin "10") (pinfunction "IO25_10") (pintype "bidirectional"))
    )
    (net (code "94") (name "unconnected-(U4-IO26-Pad11)") (class "Default")
      (node (ref "U4") (pin "11") (pinfunction "IO26_11") (pintype "bidirectional"))
    )
    (net (code "95") (name "unconnected-(U4-IO27-Pad12)") (class "Default")
      (node (ref "U4") (pin "12") (pinfunction "IO27_12") (pintype "bidirectional"))
    )
    (net (code "96") (name "unconnected-(U4-IO32-Pad8)") (class "Default")
      (node (ref "U4") (pin "8") (pinfunction "IO32_8") (pintype "bidirectional"))
    )
    (net (code "97") (name "unconnected-(U4-IO33-Pad9)") (class "Default")
      (node (ref "U4") (pin "9") (pinfunction "IO33_9") (pintype "bidirectional"))
    )
    (net (code "98") (name "unconnected-(U4-IO34-Pad6)") (class "Default")
      (node (ref "U4") (pin "6") (pinfunction "IO34_6") (pintype "input"))
    )
    (net (code "99") (name "unconnected-(U4-IO35-Pad7)") (class "Default")
      (node (ref "U4") (pin "7") (pinfunction "IO35_7") (pintype "input"))
    )
    (net (code "100") (name "unconnected-(U4-SCL{slash}CLK-Pad20)") (class "Default")
      (node (ref "U4") (pin "20") (pinfunction "SCL/CLK_20") (pintype "bidirectional"))
    )
    (net (code "101") (name "unconnected-(U4-SCS{slash}CMD-Pad19)") (class "Default")
      (node (ref "U4") (pin "19") (pinfunction "SCS/CMD_19") (pintype "bidirectional"))
    )
    (net (code "102") (name "unconnected-(U4-SDI{slash}SD1-Pad22)") (class "Default")
      (node (ref "U4") (pin "22") (pinfunction "SDI/SD1_22") (pintype "bidirectional"))
    )
    (net (code "103") (name "unconnected-(U4-SDO{slash}SD0-Pad21)") (class "Default")
      (node (ref "U4") (pin "21") (pinfunction "SDO/SD0_21") (pintype "bidirectional"))
    )
    (net (code "104") (name "unconnected-(U4-SENSOR_VN-Pad5)") (class "Default")
      (node (ref "U4") (pin "5") (pinfunction "SENSOR_VN_5") (pintype "input"))
    )
    (net (code "105") (name "unconnected-(U4-SENSOR_VP-Pad4)") (class "Default")
      (node (ref "U4") (pin "4") (pinfunction "SENSOR_VP_4") (pintype "input"))
    )
    (net (code "106") (name "unconnected-(U4-SHD{slash}SD2-Pad17)") (class "Default")
      (node (ref "U4") (pin "17") (pinfunction "SHD/SD2_17") (pintype "bidirectional"))
    )
    (net (code "107") (name "unconnected-(U4-SWP{slash}SD3-Pad18)") (class "Default")
      (node (ref "U4") (pin "18") (pinfunction "SWP/SD3_18") (pintype "bidirectional"))
    )
    (net (code "108") (name "unconnected-(U5-NC-Pad1)") (class "Default")
      (node (ref "U5") (pin "1") (pinfunction "NC_1") (pintype "bidirectional"))
    )
    (net (code "109") (name "unconnected-(U5-PadCD1)") (class "Default")
      (node (ref "U5") (pin "CD1") (pinfunction "CD1_CD1") (pintype "bidirectional"))
    )
    (net (code "110") (name "unconnected-(U5-PadCD2)") (class "Default")
      (node (ref "U5") (pin "CD2") (pinfunction "CD2_CD2") (pintype "bidirectional"))
    )
    (net (code "111") (name "unconnected-(U5-RSV-Pad8)") (class "Default")
      (node (ref "U5") (pin "8") (pinfunction "RSV_8") (pintype "bidirectional"))
    )
  )
)
